# AIL_REV2.net
KiCad netlist of a schematic drawn in Altium Designer
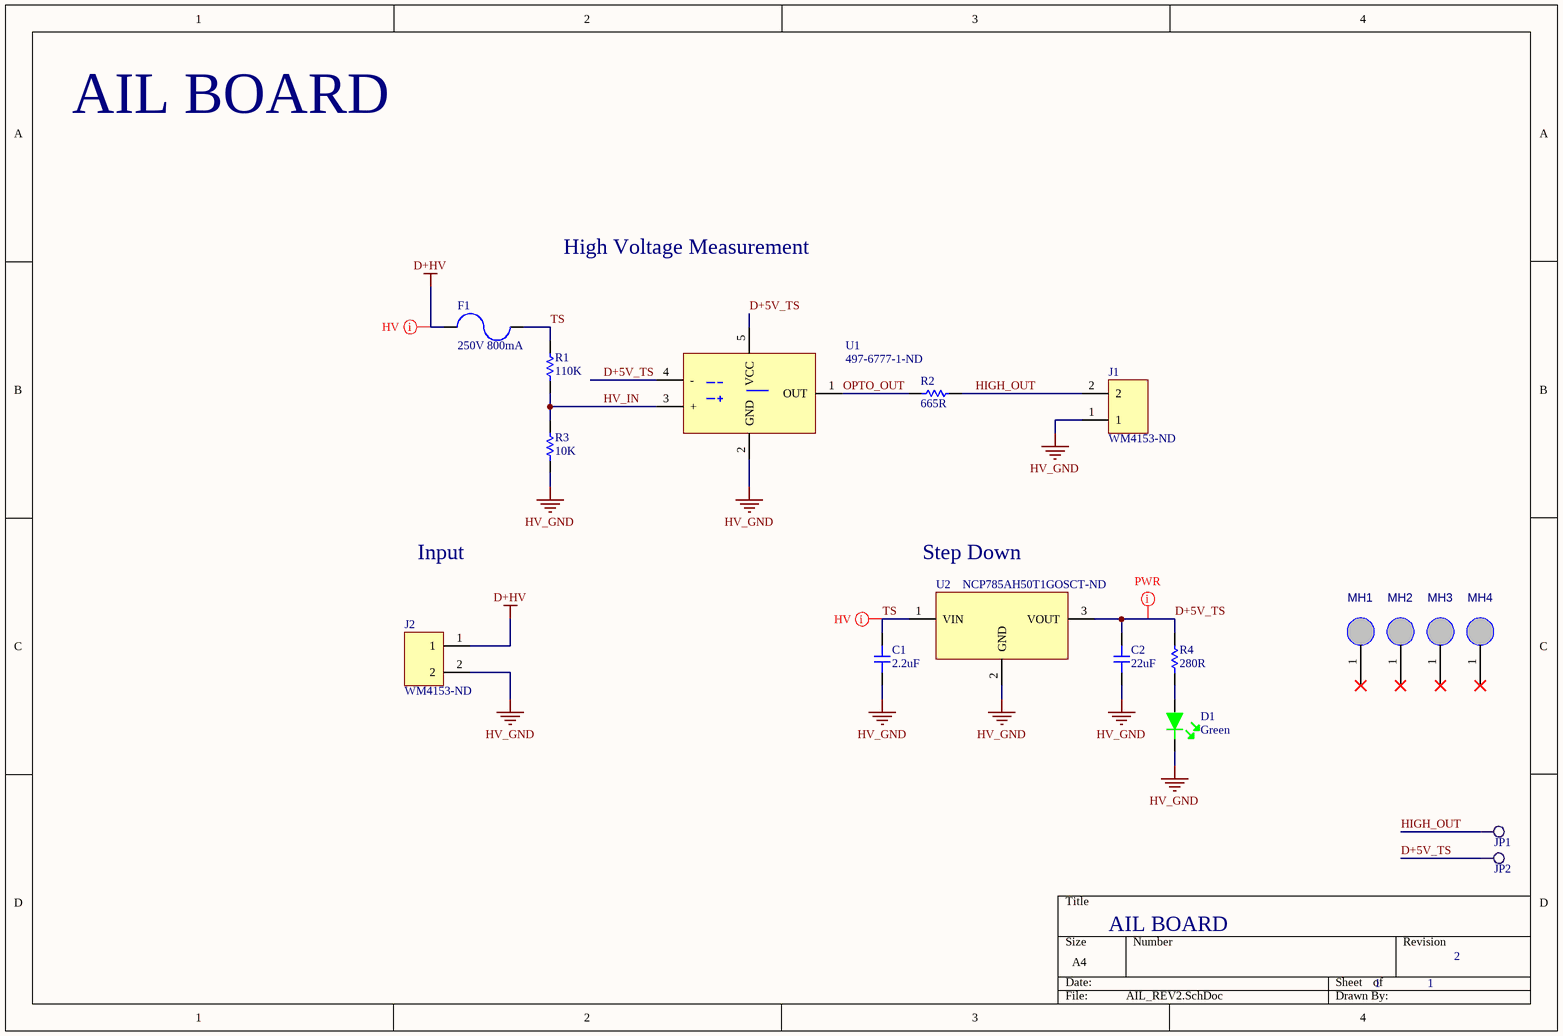
[diagram p0: AIL_REV2.SchDoc]

(export (version "E")
  (design (tool "Eeschema 10.0.6"))
  (components
    (comp (ref "C1")
      (value "2.2uF")
      (footprint "CAP-2220")
      (description "CAP CER 2.2UF 450V X6S 2220")
      (fields
        (field (name "MANUFACTURER") "TDK")
        (field (name "MANUFACTURER PART NUMBER") "C5750X6S2W225K250KA")
      )
      (libsource (lib "Capacitors") (part "2220-2.2uF-450V"))
    )
    (comp (ref "C2")
      (value "22uF")
      (footprint "CAP-0805")
      (description "CAP CER 22UF 10V X5R 0805")
      (fields
        (field (name "MANUFACTURER") "KEMET")
        (field (name "MANUFACTURER PART NUMBER") "C0805C226M8PACTU")
      )
      (libsource (lib "Capacitors") (part "0805-22uF-10V"))
    )
    (comp (ref "D1")
      (value "Green")
      (footprint "LED-0603")
      (description "LED GREEN CLEAR 0603 SMD")
      (fields
        (field (name "MANUFACTURER") "Wurth Electronics")
        (field (name "MANUFACTURER PART NUMBER") "150060VS75000")
      )
      (libsource (lib "LEDs") (part "LED-Green"))
    )
    (comp (ref "F1")
      (value "250V 800mA")
      (footprint "Fuse-10x3")
      (description "FUSE SMT 3912 FAST 250V 800MA")
      (fields (field (name "MANUFACTURER") "Bel") (field (name "MANUFACTURER PART NUMBER") "0678D0800-02"))
      (libsource (lib "Misc") (part "Fuse 250V-0.8A"))
    )
    (comp (ref "J1")
      (value "WM4153-ND")
      (footprint "2PIN")
      (description "CONN HEADER R/A 2POS 2.54MM")
      (fields (field (name "MANUFACTURER") "Molex") (field (name "MANUFACTURER PART NUMBER") "0705530106"))
      (libsource (lib "Connectors") (part "2PIN"))
    )
    (comp (ref "J2")
      (value "WM4153-ND")
      (footprint "2PIN")
      (description "CONN HEADER R/A 2POS 2.54MM")
      (fields (field (name "MANUFACTURER") "Molex") (field (name "MANUFACTURER PART NUMBER") "0705530106"))
      (libsource (lib "") (part "2PIN_1"))
    )
    (comp (ref "JP1")
      (value "Testpoint2")
      (footprint "TP2")
      (description "Single layer pad TP")
      (libsource (lib "Misc") (part "Testpoint2"))
    )
    (comp (ref "JP2")
      (value "Testpoint2")
      (footprint "TP2")
      (description "Single layer pad TP")
      (libsource (lib "Misc") (part "Testpoint2"))
    )
    (comp (ref "MH1")
      (value "MountingHole")
      (footprint "MH4.2MM")
      (description "Mounting hole, 4.2mm")
      (libsource (lib "New_Parts") (part "MH4.2mm"))
    )
    (comp (ref "MH2")
      (value "MountingHole")
      (footprint "MH4.2MM")
      (description "Mounting hole, 4.2mm")
      (libsource (lib "New_Parts") (part "MH4.2mm"))
    )
    (comp (ref "MH3")
      (value "MountingHole")
      (footprint "MH4.2MM")
      (description "Mounting hole, 4.2mm")
      (libsource (lib "New_Parts") (part "MH4.2mm"))
    )
    (comp (ref "MH4")
      (value "MountingHole")
      (footprint "MH4.2MM")
      (description "Mounting hole, 4.2mm")
      (libsource (lib "New_Parts") (part "MH4.2mm"))
    )
    (comp (ref "R1")
      (value "110K")
      (footprint "RES-0805")
      (description "RES SMD 110K OHM 1% 1/8W 0805")
      (fields
        (field (name "MANUFACTURER") "Yageo")
        (field (name "MANUFACTURER PART NUMBER") "RC0805FR-07110KL")
      )
      (libsource (lib "Resistors") (part "0805-110KR"))
    )
    (comp (ref "R2")
      (value "665R")
      (footprint "RES-0603")
      (description "RES SMD 665 OHM 1% 1/10W 0603")
      (fields
        (field (name "MANUFACTURER") "Yageo")
        (field (name "MANUFACTURER PART NUMBER") "RC0603FR-07665RL")
      )
      (libsource (lib "Resistors") (part "0603-665R"))
    )
    (comp (ref "R3")
      (value "10K")
      (footprint "RES-0805")
      (description "RES SMD 10K OHM 1% 1/8W 0805")
      (fields
        (field (name "MANUFACTURER") "Yageo")
        (field (name "MANUFACTURER PART NUMBER") "RC0805FR-0710KL")
      )
      (libsource (lib "Resistors") (part "0805-10KR"))
    )
    (comp (ref "R4")
      (value "280R")
      (footprint "RES-0805")
      (description "RES SMD 280 OHM 1% 1/8W 0805")
      (fields
        (field (name "MANUFACTURER") "Yageo")
        (field (name "MANUFACTURER PART NUMBER") "RC0805FR-07280RL")
      )
      (libsource (lib "Resistors") (part "0805-280R"))
    )
    (comp (ref "U1")
      (value "497-6777-1-ND")
      (footprint "SOT-23-5")
      (description "IC COMPARATOR R-R MCRPWR SOT23-5")
      (fields
        (field (name "MANUFACTURER") "STMicroelectronics")
        (field (name "MANUFACTURER PART NUMBER") "TS861ILT")
      )
      (libsource (lib "Logic") (part "Compare-TS861ILT"))
    )
    (comp (ref "U2")
      (value "NCP785AH50T1GOSCT-ND")
      (footprint "SOT-89")
      (description "IC REG LINEAR 5V 10MA SOT89-3")
      (fields
        (field (name "MANUFACTURER") "ON Semiconductor")
        (field (name "MANUFACTURER PART NUMBER") "NCP785AH120T1G")
      )
      (libsource (lib "Power") (part "LDO-12V-10mA"))
    )
  )
  (nets
    (net (code "1") (name "/D+5V_TS") (class "Default")
      (node (ref "C2") (pin "2") (pinfunction "2_2") (pintype "passive"))
      (node (ref "JP2") (pin "1") (pinfunction "1_1") (pintype "passive"))
      (node (ref "R4") (pin "2") (pinfunction "2_2") (pintype "passive"))
      (node (ref "U1") (pin "4") (pinfunction "-_4") (pintype "passive"))
      (node (ref "U1") (pin "5") (pinfunction "VCC_5") (pintype "passive"))
      (node (ref "U2") (pin "3") (pinfunction "VOUT_3") (pintype "passive"))
    )
    (net (code "2") (name "/HIGH_OUT") (class "Default")
      (node (ref "J1") (pin "2") (pinfunction "2_2") (pintype "passive"))
      (node (ref "JP1") (pin "1") (pinfunction "1_1") (pintype "passive"))
      (node (ref "R2") (pin "2") (pinfunction "2_2") (pintype "passive"))
    )
    (net (code "3") (name "/HV_IN") (class "Default")
      (node (ref "R1") (pin "1") (pinfunction "1_1") (pintype "passive"))
      (node (ref "R3") (pin "2") (pinfunction "2_2") (pintype "passive"))
      (node (ref "U1") (pin "3") (pinfunction "+_3") (pintype "passive"))
    )
    (net (code "4") (name "/OPTO_OUT") (class "Default")
      (node (ref "R2") (pin "1") (pinfunction "1_1") (pintype "passive"))
      (node (ref "U1") (pin "1") (pinfunction "OUT_1") (pintype "passive"))
    )
    (net (code "5") (name "/TS") (class "Default")
      (node (ref "C1") (pin "2") (pinfunction "2_2") (pintype "passive"))
      (node (ref "F1") (pin "2") (pinfunction "2_2") (pintype "passive"))
      (node (ref "R1") (pin "2") (pinfunction "2_2") (pintype "passive"))
      (node (ref "U2") (pin "1") (pinfunction "VIN_1") (pintype "passive"))
    )
    (net (code "6") (name "D+HV") (class "Default")
      (node (ref "F1") (pin "1") (pinfunction "1_1") (pintype "passive"))
      (node (ref "J2") (pin "1") (pinfunction "1_1") (pintype "passive"))
    )
    (net (code "7") (name "HV_GND") (class "Default")
      (node (ref "C1") (pin "1") (pinfunction "1_1") (pintype "passive"))
      (node (ref "C2") (pin "1") (pinfunction "1_1") (pintype "passive"))
      (node (ref "D1") (pin "2") (pinfunction "2_2") (pintype "passive"))
      (node (ref "J1") (pin "1") (pinfunction "1_1") (pintype "passive"))
      (node (ref "J2") (pin "2") (pinfunction "2_2") (pintype "passive"))
      (node (ref "R3") (pin "1") (pinfunction "1_1") (pintype "passive"))
      (node (ref "U1") (pin "2") (pinfunction "GND_2") (pintype "passive"))
      (node (ref "U2") (pin "2") (pinfunction "GND_2") (pintype "passive"))
    )
    (net (code "8") (name "Net-(D1-Pad1)") (class "Default")
      (node (ref "D1") (pin "1") (pinfunction "1_1") (pintype "passive"))
      (node (ref "R4") (pin "1") (pinfunction "1_1") (pintype "passive"))
    )
    (net (code "9") (name "unconnected-(MH1-Pad1)") (class "Default")
      (node (ref "MH1") (pin "1") (pintype "passive+no_connect"))
    )
    (net (code "10") (name "unconnected-(MH2-Pad1)") (class "Default")
      (node (ref "MH2") (pin "1") (pintype "passive+no_connect"))
    )
    (net (code "11") (name "unconnected-(MH3-Pad1)") (class "Default")
      (node (ref "MH3") (pin "1") (pintype "passive+no_connect"))
    )
    (net (code "12") (name "unconnected-(MH4-Pad1)") (class "Default")
      (node (ref "MH4") (pin "1") (pintype "passive+no_connect"))
    )
  )
)
